# BackPCB.net
KiCad netlist of a schematic drawn in Altium Designer
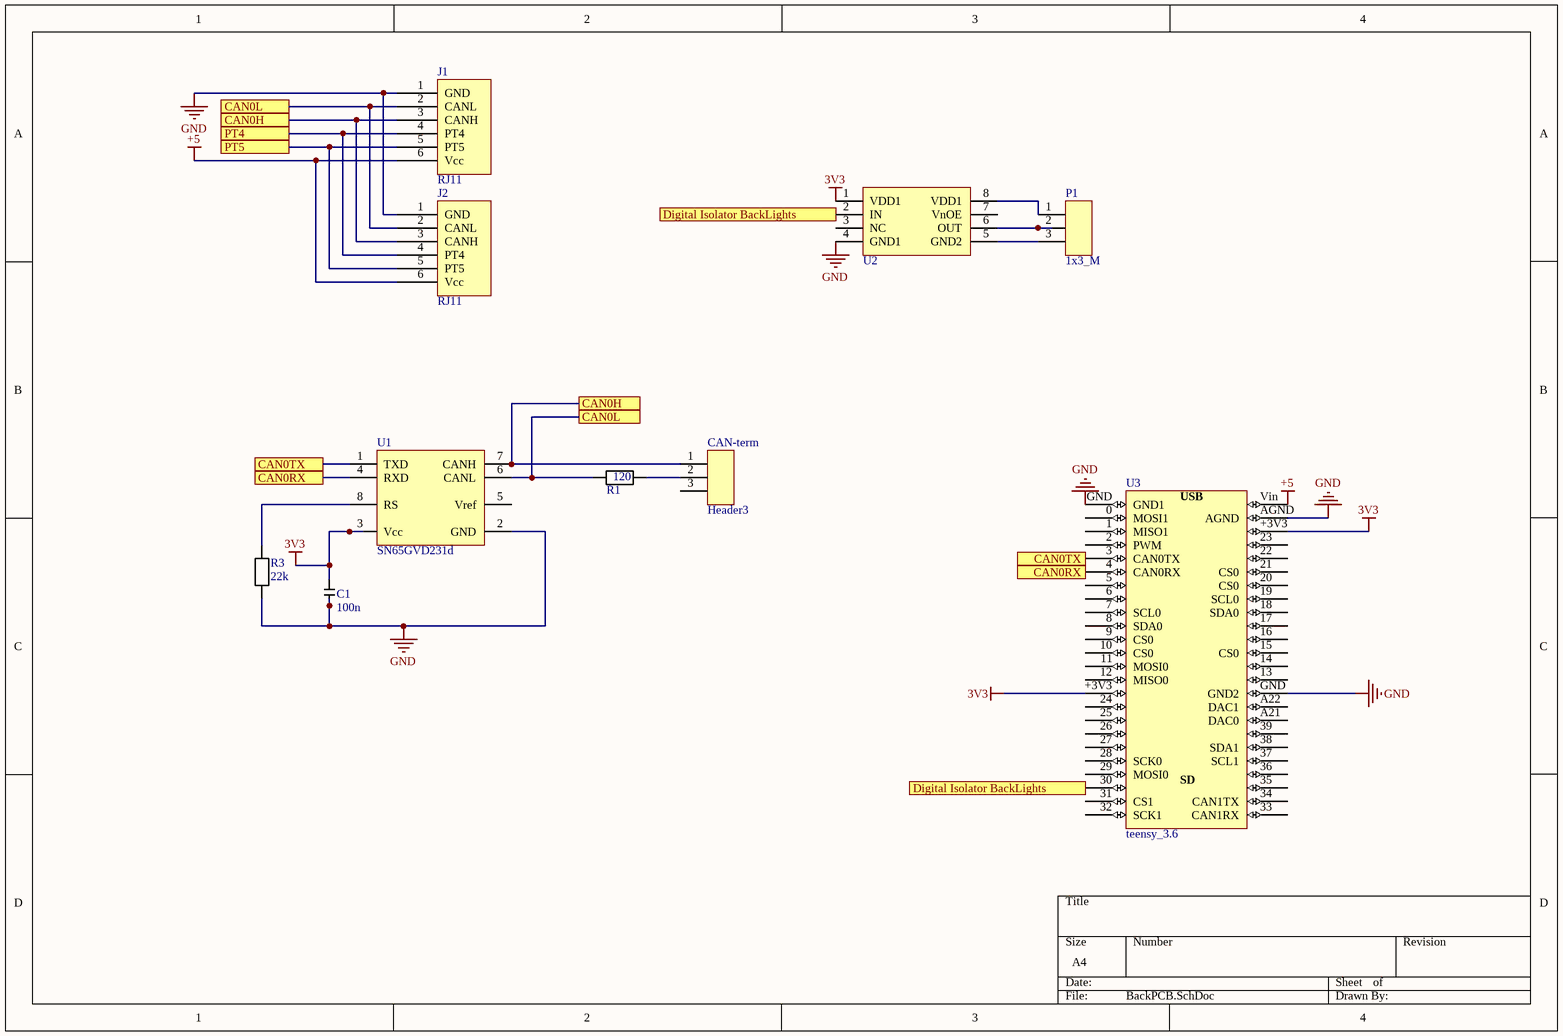
[diagram p0: BackPCB.SchDoc]

(export (version "E")
  (design (tool "Eeschema 10.0.6"))
  (components
    (comp (ref "C1")
      (value "100n")
      (footprint "C_SMD_0805_pcb")
      (fields (field (name "Comment") "SMD"))
      (libsource (lib "FF_component_lib") (part "C_SMD_0805"))
    )
    (comp (ref "CAN-term")
      (value "Header3")
      (footprint "PIN_HEADER_M_1x3")
      (libsource (lib "FF_component_lib") (part "PIN_HEADER_M_1x3"))
    )
    (comp (ref "J1")
      (value "RJ11")
      (footprint "RJ11_Connector")
      (libsource (lib "FF_component_lib") (part "RJ11_Connector"))
    )
    (comp (ref "J2")
      (value "RJ11")
      (footprint "RJ11_Connector")
      (libsource (lib "FF_component_lib") (part "RJ11_Connector"))
    )
    (comp (ref "P1")
      (value "1x3_M")
      (footprint "PIN_HEADER_M_1x3")
      (libsource (lib "FF_component_lib") (part "PIN_HEADER_M_1x3"))
    )
    (comp (ref "R1")
      (value "120")
      (footprint "R_SMD_0805_pcb")
      (fields (field (name "Comment") "SMD"))
      (libsource (lib "FF_component_lib") (part "R_SMD_0805"))
    )
    (comp (ref "R3")
      (value "22k")
      (footprint "R_SMD_0805_pcb")
      (fields (field (name "Comment") "SMD"))
      (libsource (lib "FF_component_lib") (part "R_SMD_0805"))
    )
    (comp (ref "U1")
      (value "SN65GVD231d")
      (footprint "SN65HVD231D_SMD")
      (libsource (lib "FF_component_lib") (part "SN65HVD231D_SMD"))
    )
    (comp (ref "U2")
      (value "IL_710-2E_DIGITAL_ISOLATOR")
      (footprint "IL_710-2E_DIP8")
      (description "Digital Isolator 3-5V input/output.")
      (libsource (lib "FF_component_lib") (part "IL_710-2E_DIGITAL_ISOLATOR"))
    )
    (comp (ref "U3")
      (value "teensy_3.6")
      (footprint "teensy_3.6")
      (libsource (lib "FF_component_lib") (part "teensy_3.6"))
    )
  )
  (nets
    (net (code "1") (name "+5") (class "Default")
      (node (ref "J1") (pin "6") (pinfunction "Vcc_6") (pintype "passive"))
      (node (ref "J2") (pin "6") (pinfunction "Vcc_6") (pintype "passive"))
      (node (ref "U3") (pin "Vin") (pintype "bidirectional"))
    )
    (net (code "2") (name "/CAN0H") (class "Default")
      (node (ref "CAN-term") (pin "1") (pintype "passive"))
      (node (ref "J1") (pin "3") (pinfunction "CANH_3") (pintype "passive"))
      (node (ref "J2") (pin "3") (pinfunction "CANH_3") (pintype "passive"))
      (node (ref "U1") (pin "7") (pinfunction "CANH_7") (pintype "passive"))
    )
    (net (code "3") (name "/CAN0L") (class "Default")
      (node (ref "J1") (pin "2") (pinfunction "CANL_2") (pintype "passive"))
      (node (ref "J2") (pin "2") (pinfunction "CANL_2") (pintype "passive"))
      (node (ref "R1") (pin "1") (pinfunction "1_1") (pintype "passive"))
      (node (ref "U1") (pin "6") (pinfunction "CANL_6") (pintype "passive"))
    )
    (net (code "4") (name "/CAN0RX") (class "Default")
      (node (ref "U1") (pin "4") (pinfunction "RXD_4") (pintype "passive"))
      (node (ref "U3") (pin "4") (pinfunction "CAN0RX_4") (pintype "bidirectional"))
    )
    (net (code "5") (name "/CAN0TX") (class "Default")
      (node (ref "U1") (pin "1") (pinfunction "TXD_1") (pintype "passive"))
      (node (ref "U3") (pin "3") (pinfunction "CAN0TX_3") (pintype "bidirectional"))
    )
    (net (code "6") (name "/Digital Isolator BackLights") (class "Default")
      (node (ref "U2") (pin "2") (pinfunction "IN_2") (pintype "passive"))
      (node (ref "U3") (pin "30") (pintype "bidirectional"))
    )
    (net (code "7") (name "/PT4") (class "Default")
      (node (ref "J1") (pin "4") (pinfunction "PT4_4") (pintype "passive"))
      (node (ref "J2") (pin "4") (pinfunction "PT4_4") (pintype "passive"))
    )
    (net (code "8") (name "/PT5") (class "Default")
      (node (ref "J1") (pin "5") (pinfunction "PT5_5") (pintype "passive"))
      (node (ref "J2") (pin "5") (pinfunction "PT5_5") (pintype "passive"))
    )
    (net (code "9") (name "3V3") (class "Default")
      (node (ref "C1") (pin "1") (pinfunction "1_1") (pintype "passive"))
      (node (ref "U1") (pin "3") (pinfunction "Vcc_3") (pintype "passive"))
      (node (ref "U2") (pin "1") (pinfunction "VDD1_1") (pintype "passive"))
      (node (ref "U3") (pin "+3V3") (pintype "bidirectional"))
    )
    (net (code "10") (name "GND") (class "Default")
      (node (ref "C1") (pin "2") (pinfunction "2_2") (pintype "passive"))
      (node (ref "J1") (pin "1") (pinfunction "GND_1") (pintype "passive"))
      (node (ref "J2") (pin "1") (pinfunction "GND_1") (pintype "passive"))
      (node (ref "R3") (pin "1") (pinfunction "1_1") (pintype "passive"))
      (node (ref "U1") (pin "2") (pinfunction "GND_2") (pintype "passive"))
      (node (ref "U2") (pin "4") (pinfunction "GND1_4") (pintype "passive"))
      (node (ref "U3") (pin "AGND") (pinfunction "AGND_AGND") (pintype "bidirectional"))
      (node (ref "U3") (pin "GND") (pinfunction "GND1_GND") (pintype "bidirectional"))
    )
    (net (code "11") (name "Net-(CAN-term-Pad2)") (class "Default")
      (node (ref "CAN-term") (pin "2") (pintype "passive"))
      (node (ref "R1") (pin "2") (pinfunction "2_2") (pintype "passive"))
    )
    (net (code "12") (name "Net-(P1-Pad1)") (class "Default")
      (node (ref "P1") (pin "1") (pintype "passive"))
      (node (ref "U2") (pin "8") (pinfunction "VDD1_8") (pintype "passive"))
    )
    (net (code "13") (name "Net-(U1-RS)") (class "Default")
      (node (ref "R3") (pin "2") (pinfunction "2_2") (pintype "passive"))
      (node (ref "U1") (pin "8") (pinfunction "RS_8") (pintype "passive"))
    )
    (net (code "14") (name "Net-(U2-GND2)") (class "Default")
      (node (ref "P1") (pin "3") (pintype "passive"))
      (node (ref "U2") (pin "5") (pinfunction "GND2_5") (pintype "passive"))
    )
    (net (code "15") (name "Net-(U2-OUT)") (class "Default")
      (node (ref "P1") (pin "2") (pintype "passive"))
      (node (ref "U2") (pin "6") (pinfunction "OUT_6") (pintype "passive"))
    )
    (net (code "16") (name "unconnected-(CAN-term-Pad3)") (class "Default")
      (node (ref "CAN-term") (pin "3") (pintype "passive"))
    )
    (net (code "17") (name "unconnected-(U1-Vref-Pad5)") (class "Default")
      (node (ref "U1") (pin "5") (pinfunction "Vref_5") (pintype "passive"))
    )
    (net (code "18") (name "unconnected-(U2-NC-Pad3)") (class "Default")
      (node (ref "U2") (pin "3") (pinfunction "NC_3") (pintype "passive"))
    )
    (net (code "19") (name "unconnected-(U2-VnOE-Pad7)") (class "Default")
      (node (ref "U2") (pin "7") (pinfunction "VnOE_7") (pintype "passive"))
    )
    (net (code "20") (name "unconnected-(U3-CAN1RX-Pad33)") (class "Default")
      (node (ref "U3") (pin "33") (pinfunction "CAN1RX_33") (pintype "bidirectional"))
    )
    (net (code "21") (name "unconnected-(U3-CAN1TX-Pad34)") (class "Default")
      (node (ref "U3") (pin "34") (pinfunction "CAN1TX_34") (pintype "bidirectional"))
    )
    (net (code "22") (name "unconnected-(U3-CS0-Pad9)") (class "Default")
      (node (ref "U3") (pin "9") (pinfunction "CS0_9") (pintype "bidirectional"))
    )
    (net (code "23") (name "unconnected-(U3-CS0-Pad10)") (class "Default")
      (node (ref "U3") (pin "10") (pinfunction "CS0_10") (pintype "bidirectional"))
    )
    (net (code "24") (name "unconnected-(U3-CS0-Pad15)") (class "Default")
      (node (ref "U3") (pin "15") (pinfunction "CS0_15") (pintype "bidirectional"))
    )
    (net (code "25") (name "unconnected-(U3-CS0-Pad20)") (class "Default")
      (node (ref "U3") (pin "20") (pinfunction "CS0_20") (pintype "bidirectional"))
    )
    (net (code "26") (name "unconnected-(U3-CS0-Pad21)") (class "Default")
      (node (ref "U3") (pin "21") (pinfunction "CS0_21") (pintype "bidirectional"))
    )
    (net (code "27") (name "unconnected-(U3-CS1-Pad31)") (class "Default")
      (node (ref "U3") (pin "31") (pinfunction "CS1_31") (pintype "bidirectional"))
    )
    (net (code "28") (name "unconnected-(U3-DAC0-PadA21)") (class "Default")
      (node (ref "U3") (pin "A21") (pinfunction "DAC0_A21") (pintype "bidirectional"))
    )
    (net (code "29") (name "unconnected-(U3-DAC1-PadA22)") (class "Default")
      (node (ref "U3") (pin "A22") (pinfunction "DAC1_A22") (pintype "bidirectional"))
    )
    (net (code "30") (name "unconnected-(U3-MISO0-Pad12)") (class "Default")
      (node (ref "U3") (pin "12") (pinfunction "MISO0_12") (pintype "bidirectional"))
    )
    (net (code "31") (name "unconnected-(U3-MISO1-Pad1)") (class "Default")
      (node (ref "U3") (pin "1") (pinfunction "MISO1_1") (pintype "bidirectional"))
    )
    (net (code "32") (name "unconnected-(U3-MOSI0-Pad11)") (class "Default")
      (node (ref "U3") (pin "11") (pinfunction "MOSI0_11") (pintype "bidirectional"))
    )
    (net (code "33") (name "unconnected-(U3-MOSI0-Pad29)") (class "Default")
      (node (ref "U3") (pin "29") (pinfunction "MOSI0_29") (pintype "bidirectional"))
    )
    (net (code "34") (name "unconnected-(U3-MOSI1-Pad0)") (class "Default")
      (node (ref "U3") (pin "0") (pinfunction "MOSI1_0") (pintype "bidirectional"))
    )
    (net (code "35") (name "unconnected-(U3-PWM-Pad2)") (class "Default")
      (node (ref "U3") (pin "2") (pinfunction "PWM_2") (pintype "bidirectional"))
    )
    (net (code "36") (name "unconnected-(U3-Pad5)") (class "Default")
      (node (ref "U3") (pin "5") (pintype "bidirectional"))
    )
    (net (code "37") (name "unconnected-(U3-Pad6)") (class "Default")
      (node (ref "U3") (pin "6") (pintype "bidirectional"))
    )
    (net (code "38") (name "unconnected-(U3-Pad13)") (class "Default")
      (node (ref "U3") (pin "13") (pintype "bidirectional"))
    )
    (net (code "39") (name "unconnected-(U3-Pad14)") (class "Default")
      (node (ref "U3") (pin "14") (pintype "bidirectional"))
    )
    (net (code "40") (name "unconnected-(U3-Pad16)") (class "Default")
      (node (ref "U3") (pin "16") (pintype "bidirectional"))
    )
    (net (code "41") (name "unconnected-(U3-Pad17)") (class "Default")
      (node (ref "U3") (pin "17") (pintype "bidirectional"))
    )
    (net (code "42") (name "unconnected-(U3-Pad22)") (class "Default")
      (node (ref "U3") (pin "22") (pintype "bidirectional"))
    )
    (net (code "43") (name "unconnected-(U3-Pad23)") (class "Default")
      (node (ref "U3") (pin "23") (pintype "bidirectional"))
    )
    (net (code "44") (name "unconnected-(U3-Pad24)") (class "Default")
      (node (ref "U3") (pin "24") (pintype "bidirectional"))
    )
    (net (code "45") (name "unconnected-(U3-Pad25)") (class "Default")
      (node (ref "U3") (pin "25") (pintype "bidirectional"))
    )
    (net (code "46") (name "unconnected-(U3-Pad26)") (class "Default")
      (node (ref "U3") (pin "26") (pintype "bidirectional"))
    )
    (net (code "47") (name "unconnected-(U3-Pad27)") (class "Default")
      (node (ref "U3") (pin "27") (pintype "bidirectional"))
    )
    (net (code "48") (name "unconnected-(U3-Pad35)") (class "Default")
      (node (ref "U3") (pin "35") (pintype "bidirectional"))
    )
    (net (code "49") (name "unconnected-(U3-Pad36)") (class "Default")
      (node (ref "U3") (pin "36") (pintype "bidirectional"))
    )
    (net (code "50") (name "unconnected-(U3-Pad39)") (class "Default")
      (node (ref "U3") (pin "39") (pintype "bidirectional"))
    )
    (net (code "51") (name "unconnected-(U3-SCK0-Pad28)") (class "Default")
      (node (ref "U3") (pin "28") (pinfunction "SCK0_28") (pintype "bidirectional"))
    )
    (net (code "52") (name "unconnected-(U3-SCK1-Pad32)") (class "Default")
      (node (ref "U3") (pin "32") (pinfunction "SCK1_32") (pintype "bidirectional"))
    )
    (net (code "53") (name "unconnected-(U3-SCL0-Pad7)") (class "Default")
      (node (ref "U3") (pin "7") (pinfunction "SCL0_7") (pintype "bidirectional"))
    )
    (net (code "54") (name "unconnected-(U3-SCL0-Pad19)") (class "Default")
      (node (ref "U3") (pin "19") (pinfunction "SCL0_19") (pintype "bidirectional"))
    )
    (net (code "55") (name "unconnected-(U3-SCL1-Pad37)") (class "Default")
      (node (ref "U3") (pin "37") (pinfunction "SCL1_37") (pintype "bidirectional"))
    )
    (net (code "56") (name "unconnected-(U3-SDA0-Pad8)") (class "Default")
      (node (ref "U3") (pin "8") (pinfunction "SDA0_8") (pintype "bidirectional"))
    )
    (net (code "57") (name "unconnected-(U3-SDA0-Pad18)") (class "Default")
      (node (ref "U3") (pin "18") (pinfunction "SDA0_18") (pintype "bidirectional"))
    )
    (net (code "58") (name "unconnected-(U3-SDA1-Pad38)") (class "Default")
      (node (ref "U3") (pin "38") (pinfunction "SDA1_38") (pintype "bidirectional"))
    )
  )
)
